# SipPuffOneOuputATtiny85MOSFET.net
KiCad netlist of a schematic drawn in EAGLE
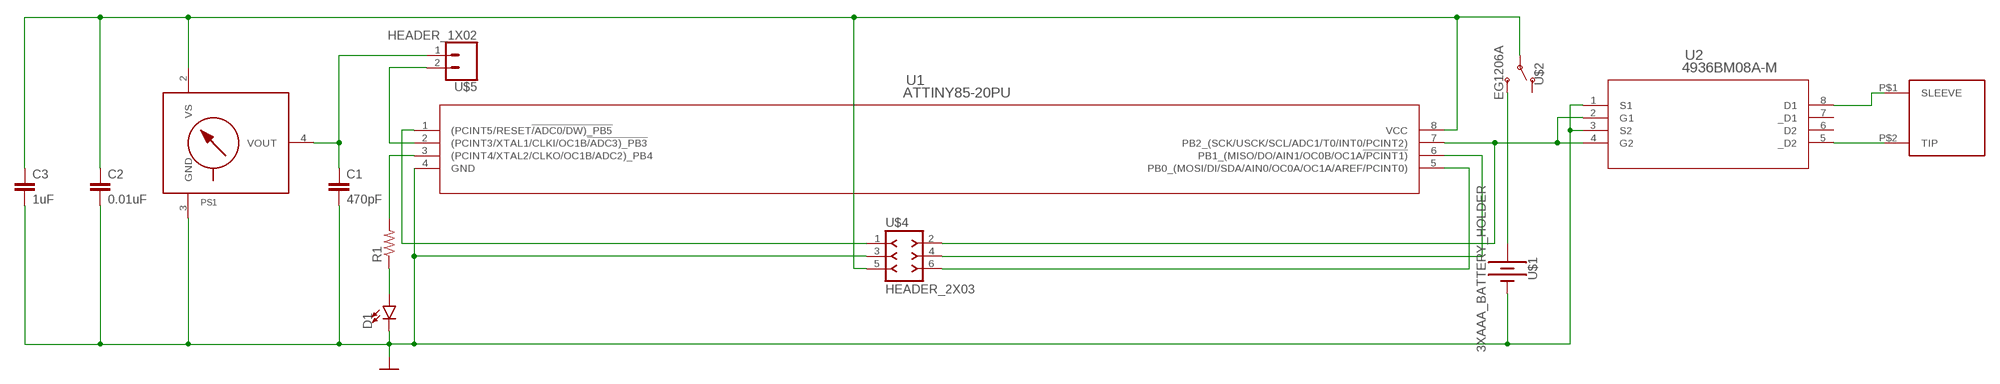
[diagram p0: schematic, sheet 1]

(export (version "E")
  (design (tool "Eeschema 10.0.6"))
  (components
    (comp (ref "C1")
      (value "470pF")
      (footprint "eagle-import:CAP-PTH-SMALL-KIT")
      (libsource (lib "eagle-import") (part "0.1UF-KIT-EZ-50V-20%"))
    )
    (comp (ref "C2")
      (value "0.01uF")
      (footprint "eagle-import:CAP-PTH-SMALL-KIT")
      (libsource (lib "eagle-import") (part "0.1UF-KIT-EZ-50V-20%"))
    )
    (comp (ref "C3")
      (value "1uF")
      (footprint "eagle-import:CAP-PTH-SMALL-KIT")
      (libsource (lib "eagle-import") (part "0.1UF-KIT-EZ-50V-20%"))
    )
    (comp (ref "D1")
      (value "LED5MM")
      (footprint "eagle-import:LED_5MM")
      (libsource (lib "eagle-import") (part "LED5MM"))
    )
    (comp (ref "PS1")
      (value "MPX-1351")
      (footprint "eagle-import:1351")
      (libsource (lib "eagle-import") (part "MPX-1351"))
    )
    (comp (ref "R1")
      (value "RESISTOR_R-US_")
      (footprint "eagle-import:RESISTOR_0207_10")
      (libsource (lib "eagle-import") (part "RESISTOR_R-US_"))
    )
    (comp (ref "U$1")
      (value "3XAAA_BATTERY_HOLDER")
      (footprint "eagle-import:3XAAA_BATTERY_HOLDER")
      (libsource (lib "eagle-import") (part "3XAAA_BATTERY_HOLDER"))
    )
    (comp (ref "U$2")
      (value "EG1206A")
      (footprint "eagle-import:EG1206A")
      (libsource (lib "eagle-import") (part "EG1206A"))
    )
    (comp (ref "U$3")
      (value "MONO_WIRE")
      (footprint "eagle-import:MONO_WIRE")
      (libsource (lib "eagle-import") (part "MONO_WIRE"))
    )
    (comp (ref "U$4")
      (value "HEADER_2X03")
      (footprint "eagle-import:2X3")
      (libsource (lib "eagle-import") (part "HEADER_2X03"))
    )
    (comp (ref "U$5")
      (value "HEADER_1X02")
      (footprint "eagle-import:1X02")
      (libsource (lib "eagle-import") (part "HEADER_1X02"))
    )
    (comp (ref "U1")
      (value "ATTINY85-20PU")
      (footprint "eagle-import:8P3")
      (fields (field (name "MANUFACTURER_PART_NUMBER") "ATTINY8520PU"))
      (libsource (lib "eagle-import") (part "ATTINY85-20PU"))
    )
    (comp (ref "U2")
      (value "4936BM08A-M")
      (footprint "eagle-import:M08A-M")
      (fields (field (name "MANUFACTURER_PART_NUMBER") "LM34DM"))
      (libsource (lib "eagle-import") (part "4936BM08A-M"))
    )
  )
  (nets
    (net (code "1") (name "GND") (class "Default")
      (node (ref "C1") (pin "2") (pinfunction "2_2") (pintype "passive"))
      (node (ref "C2") (pin "2") (pinfunction "2_2") (pintype "passive"))
      (node (ref "C3") (pin "2") (pinfunction "2_2") (pintype "passive"))
      (node (ref "D1") (pin "K") (pinfunction "C_K") (pintype "passive"))
      (node (ref "PS1") (pin "3") (pinfunction "GND_3") (pintype "power_in"))
      (node (ref "U$1") (pin "P$2") (pinfunction "-_P$2") (pintype "power_in"))
      (node (ref "U$4") (pin "3") (pinfunction "3_3") (pintype "passive"))
      (node (ref "U1") (pin "4") (pinfunction "GND_4") (pintype "power_in"))
      (node (ref "U2") (pin "1") (pinfunction "S1_1") (pintype "output"))
      (node (ref "U2") (pin "3") (pinfunction "S2_3") (pintype "passive"))
    )
    (net (code "2") (name "Net-(D1-PadA)") (class "Default")
      (node (ref "D1") (pin "A") (pinfunction "A_A") (pintype "passive"))
      (node (ref "R1") (pin "1") (pinfunction "1_1") (pintype "passive"))
    )
    (net (code "3") (name "Net-(PS1-VOUT)") (class "Default")
      (node (ref "C1") (pin "1") (pinfunction "1_1") (pintype "passive"))
      (node (ref "PS1") (pin "4") (pinfunction "VOUT_4") (pintype "output"))
      (node (ref "U$5") (pin "1") (pinfunction "1_1") (pintype "passive"))
    )
    (net (code "4") (name "Net-(PS1-VS)") (class "Default")
      (node (ref "C2") (pin "1") (pinfunction "1_1") (pintype "passive"))
      (node (ref "C3") (pin "1") (pinfunction "1_1") (pintype "passive"))
      (node (ref "PS1") (pin "2") (pinfunction "VS_2") (pintype "power_in"))
      (node (ref "U$2") (pin "2") (pinfunction "P_2") (pintype "passive"))
      (node (ref "U$4") (pin "5") (pinfunction "5_5") (pintype "passive"))
      (node (ref "U1") (pin "8") (pinfunction "VCC_8") (pintype "power_in"))
    )
    (net (code "5") (name "Net-(U$1-+)") (class "Default")
      (node (ref "U$1") (pin "P$1") (pinfunction "+_P$1") (pintype "power_in"))
      (node (ref "U$2") (pin "3") (pinfunction "S_3") (pintype "passive"))
    )
    (net (code "6") (name "Net-(U$3-SLEEVE)") (class "Default")
      (node (ref "U$3") (pin "P$1") (pinfunction "SLEEVE_P$1") (pintype "bidirectional"))
      (node (ref "U2") (pin "8") (pinfunction "D1_8") (pintype "input"))
    )
    (net (code "7") (name "Net-(U$3-TIP)") (class "Default")
      (node (ref "U$3") (pin "P$2") (pinfunction "TIP_P$2") (pintype "bidirectional"))
      (node (ref "U2") (pin "5") (pinfunction "_D2_5") (pintype "passive"))
    )
    (net (code "8") (name "Net-(U1-(PCINT3{slash}XTAL1{slash}CLKI{slash}OC1B~{{slash}ADC3})_PB3)") (class "Default")
      (node (ref "U$5") (pin "2") (pinfunction "2_2") (pintype "passive"))
      (node (ref "U1") (pin "2") (pinfunction "(PCINT3/XTAL1/CLKI/OC1B~{/ADC3})_PB3_2") (pintype "bidirectional"))
    )
    (net (code "9") (name "Net-(U1-(PCINT4{slash}XTAL2{slash}CLKO{slash}OC1B{slash}ADC2)_PB4)") (class "Default")
      (node (ref "R1") (pin "2") (pinfunction "2_2") (pintype "passive"))
      (node (ref "U1") (pin "3") (pinfunction "(PCINT4/XTAL2/CLKO/OC1B/ADC2)_PB4_3") (pintype "bidirectional"))
    )
    (net (code "10") (name "Net-(U1-(PCINT5{slash}RESET~{{slash}ADC0{slash}DW})_PB5)") (class "Default")
      (node (ref "U$4") (pin "1") (pinfunction "1_1") (pintype "passive"))
      (node (ref "U1") (pin "1") (pinfunction "(PCINT5/RESET~{/ADC0/DW})_PB5_1") (pintype "bidirectional"))
    )
    (net (code "11") (name "Net-(U1-PB0_(MOSI{slash}DI{slash}SDA{slash}AIN0{slash}OC0A{slash}OC1A{slash}AREF{slash}PCINT0))") (class "Default")
      (node (ref "U$4") (pin "6") (pinfunction "6_6") (pintype "passive"))
      (node (ref "U1") (pin "5") (pinfunction "PB0_(MOSI/DI/SDA/AIN0/OC0A/OC1A/AREF/PCINT0)_5") (pintype "bidirectional"))
    )
    (net (code "12") (name "Net-(U1-PB1_(MISO{slash}DO{slash}AIN1{slash}OC0B{slash}OC1A~{{slash}PCINT1}))") (class "Default")
      (node (ref "U$4") (pin "4") (pinfunction "4_4") (pintype "passive"))
      (node (ref "U1") (pin "6") (pinfunction "PB1_(MISO/DO/AIN1/OC0B/OC1A~{/PCINT1})_6") (pintype "bidirectional"))
    )
    (net (code "13") (name "Net-(U1-PB2_(SCK{slash}USCK{slash}SCL{slash}ADC1{slash}T0{slash}INT0{slash}PCINT2))") (class "Default")
      (node (ref "U$4") (pin "2") (pinfunction "2_2") (pintype "passive"))
      (node (ref "U1") (pin "7") (pinfunction "PB2_(SCK/USCK/SCL/ADC1/T0/INT0/PCINT2)_7") (pintype "bidirectional"))
      (node (ref "U2") (pin "2") (pinfunction "G1_2") (pintype "passive"))
      (node (ref "U2") (pin "4") (pinfunction "G2_4") (pintype "power_in"))
    )
    (net (code "14") (name "unconnected-(PS1-NC-Pad1)") (class "Default")
      (node (ref "PS1") (pin "1") (pinfunction "NC_1") (pintype "no_connect"))
    )
    (net (code "15") (name "unconnected-(PS1-NC-Pad5)") (class "Default")
      (node (ref "PS1") (pin "5") (pinfunction "NC_5") (pintype "no_connect"))
    )
    (net (code "16") (name "unconnected-(PS1-NC-Pad6)") (class "Default")
      (node (ref "PS1") (pin "6") (pinfunction "NC_6") (pintype "no_connect"))
    )
    (net (code "17") (name "unconnected-(U$2-O-Pad1)") (class "Default")
      (node (ref "U$2") (pin "1") (pinfunction "O_1") (pintype "passive"))
    )
    (net (code "18") (name "unconnected-(U2-D2-Pad6)") (class "Default")
      (node (ref "U2") (pin "6") (pinfunction "D2_6") (pintype "passive"))
    )
    (net (code "19") (name "unconnected-(U2-_D1-Pad7)") (class "Default")
      (node (ref "U2") (pin "7") (pinfunction "_D1_7") (pintype "passive"))
    )
  )
)
